# mimxrt10xx.net
KiCad netlist of a schematic drawn in Altium Designer
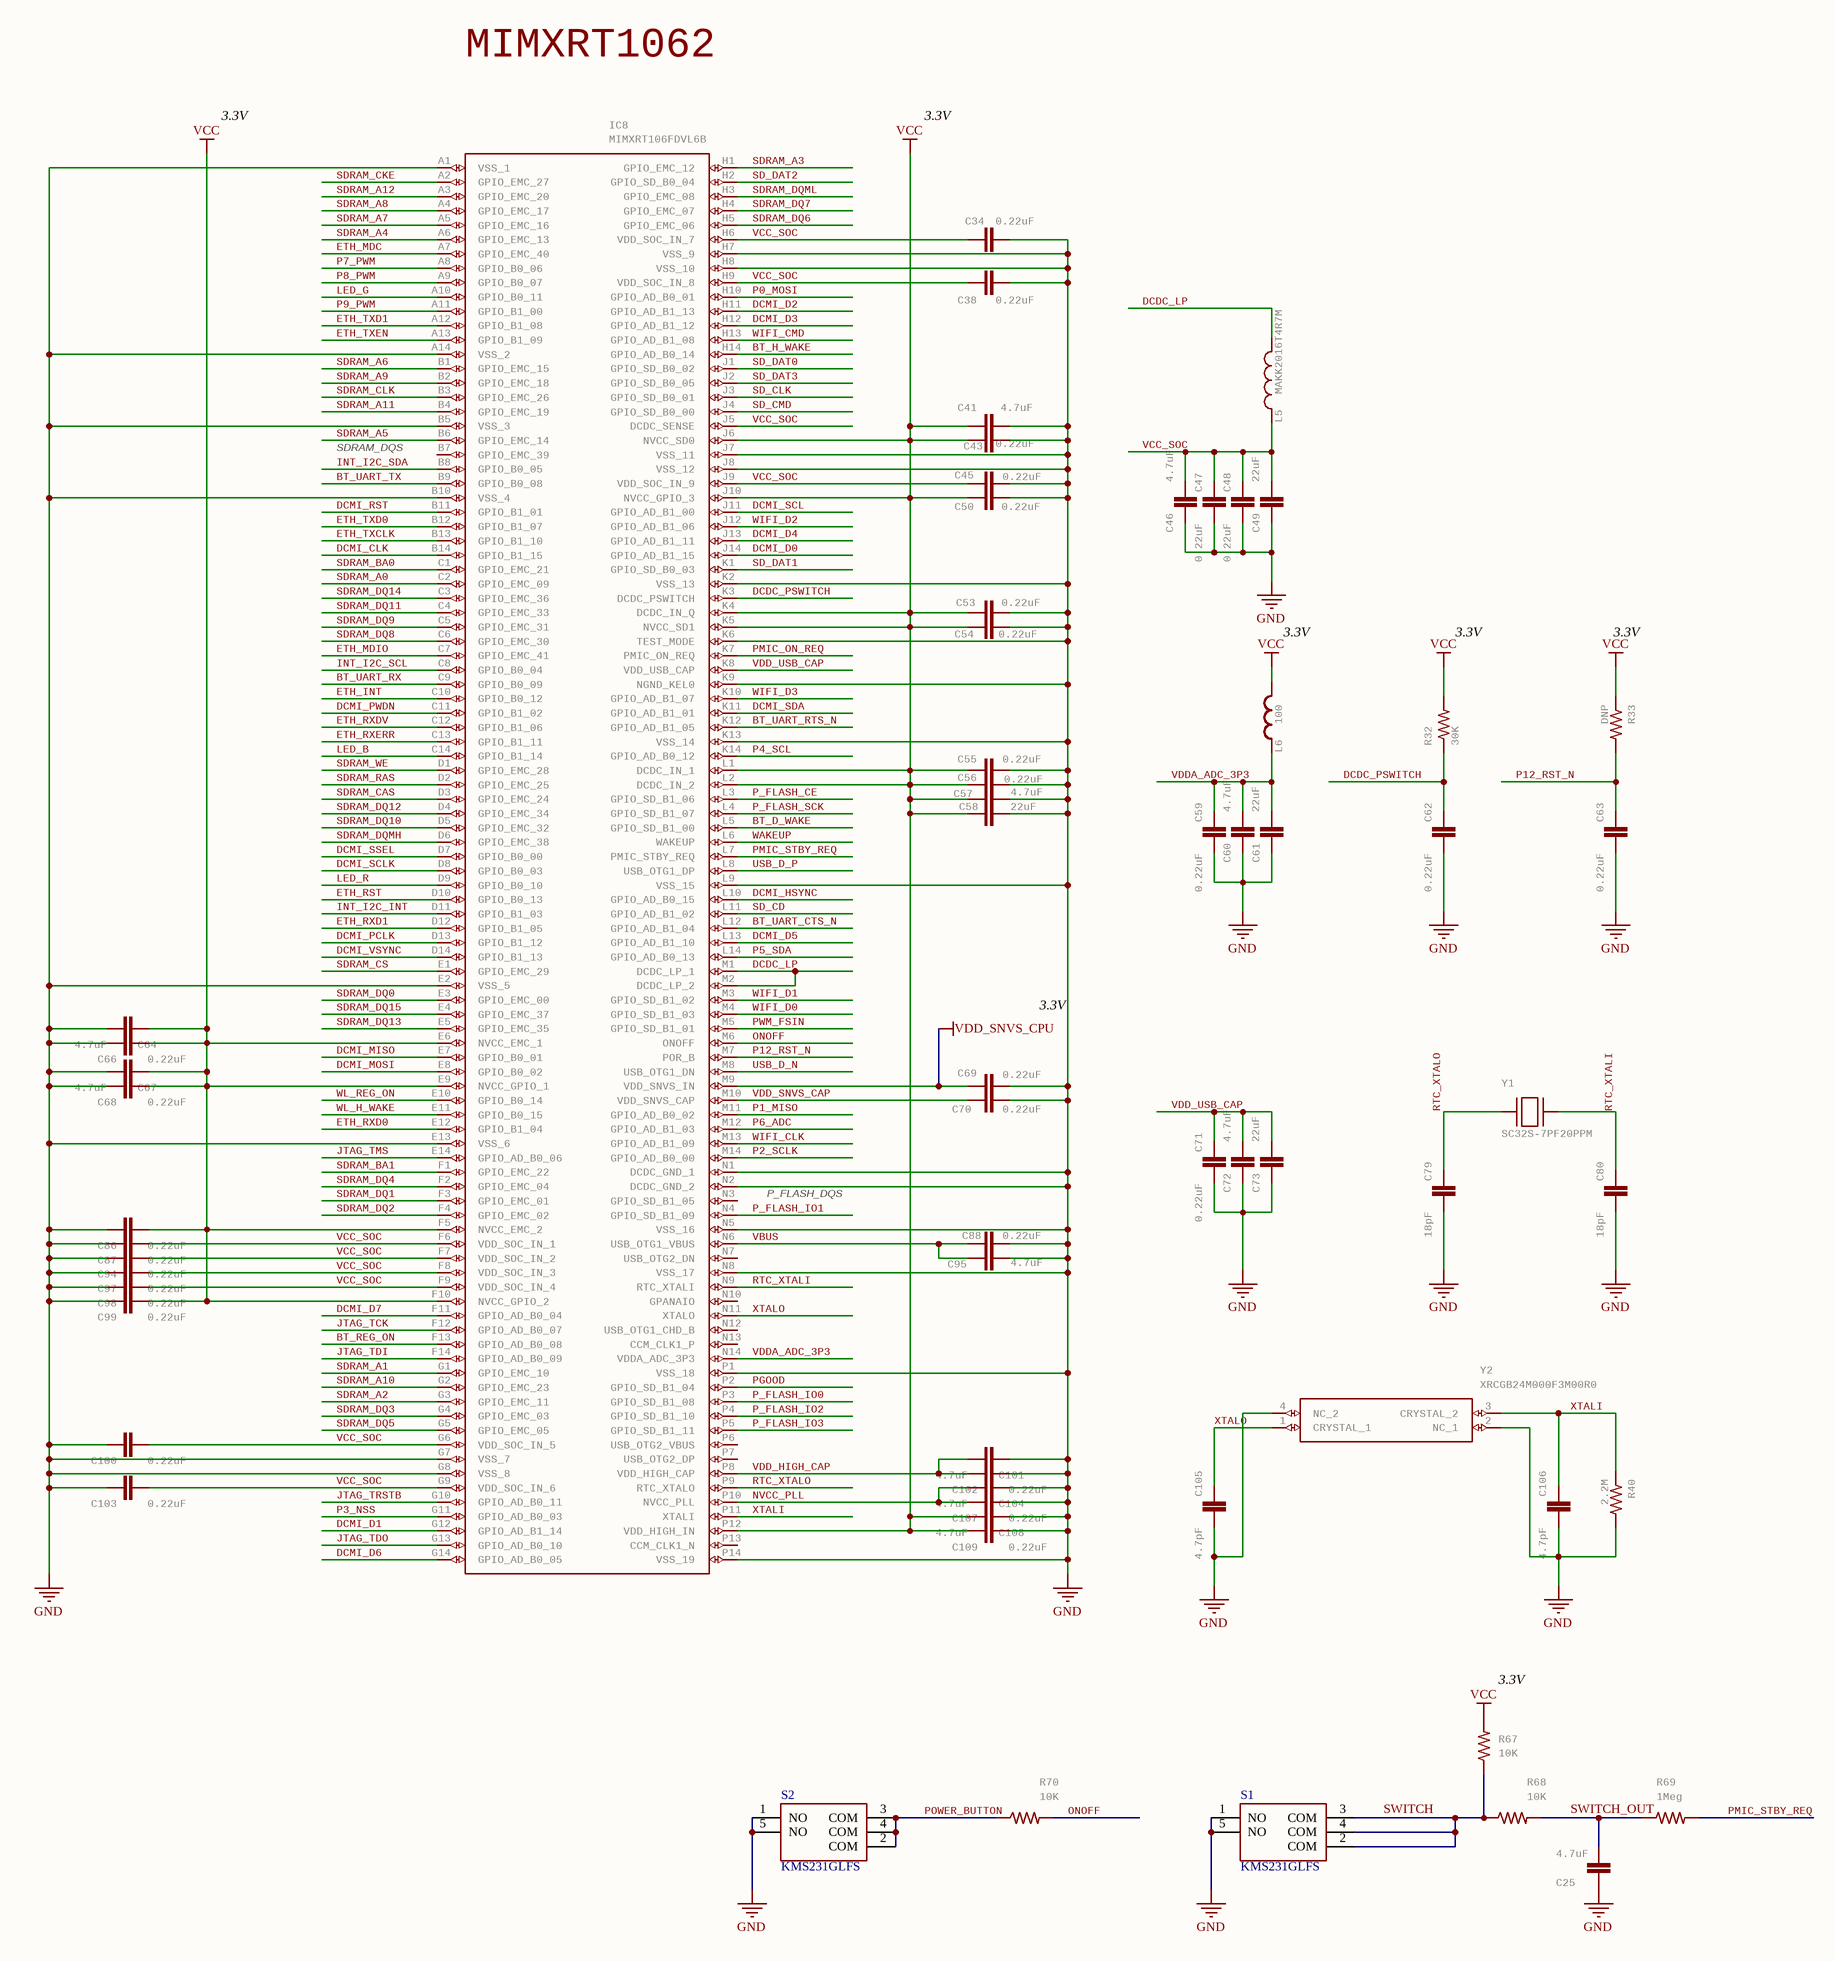
[diagram p0: mimxrt10xx.SchDoc]

(export (version "E")
  (design (tool "Eeschema 10.0.6"))
  (components
    (comp (ref "C25")
      (value "4.7uF")
      (footprint "0402-CAP")
      (description "CapacitorStandard 0603 ceramic capacitor, and 0.1\" leaded capacitor.")
      (fields (field (name "MPN") "JMK105BBJ475MV-F"))
      (libsource (lib "") (part "CAP0402-CAP_1"))
    )
    (comp (ref "C34")
      (value "0.22uF")
      (footprint "C0201")
      (description "CAPACITOR, European symbol")
      (fields (field (name "MPN") "GRM033R60J224ME15D"))
      (libsource (lib "rt10") (part "C-EUC0201"))
    )
    (comp (ref "C38")
      (value "0.22uF")
      (footprint "C0201")
      (description "CAPACITOR, European symbol")
      (fields (field (name "MPN") "GRM033R60J224ME15D"))
      (libsource (lib "rt10") (part "C-EUC0201"))
    )
    (comp (ref "C41")
      (value "4.7uF")
      (footprint "0402-CAP")
      (description "CapacitorStandard 0603 ceramic capacitor, and 0.1\" leaded capacitor.")
      (fields (field (name "MPN") "JMK105BBJ475MV-F"))
      (libsource (lib "rt10") (part "CAP0402-CAP"))
    )
    (comp (ref "C43")
      (value "0.22uF")
      (footprint "C0201")
      (description "CAPACITOR, European symbol")
      (fields (field (name "MPN") "GRM033R60J224ME15D"))
      (libsource (lib "rt10") (part "C-EUC0201"))
    )
    (comp (ref "C45")
      (value "0.22uF")
      (footprint "C0201")
      (description "CAPACITOR, European symbol")
      (fields (field (name "MPN") "GRM033R60J224ME15D"))
      (libsource (lib "rt10") (part "C-EUC0201"))
    )
    (comp (ref "C46")
      (value "4.7uF")
      (footprint "0402-CAP")
      (description "CapacitorStandard 0603 ceramic capacitor, and 0.1\" leaded capacitor.")
      (fields (field (name "MPN") "JMK105BBJ475MV-F"))
      (libsource (lib "") (part "CAP0402-CAP_1"))
    )
    (comp (ref "C47")
      (value "0.22uF")
      (footprint "C0201")
      (description "CAPACITOR, European symbol")
      (fields (field (name "MPN") "GRM033R60J224ME15D"))
      (libsource (lib "") (part "C-EUC0201_1"))
    )
    (comp (ref "C48")
      (value "0.22uF")
      (footprint "C0201")
      (description "CAPACITOR, European symbol")
      (fields (field (name "MPN") "GRM033R60J224ME15D"))
      (libsource (lib "") (part "C-EUC0201_1"))
    )
    (comp (ref "C49")
      (value "22uF")
      (footprint "0805")
      (fields (field (name "MPN") "CL21A226MQQNNNE"))
      (libsource (lib "rt10") (part "22UF-0805-6.3V-20%"))
    )
    (comp (ref "C50")
      (value "0.22uF")
      (footprint "C0201")
      (description "CAPACITOR, European symbol")
      (fields (field (name "MPN") "GRM033R60J224ME15D"))
      (libsource (lib "rt10") (part "C-EUC0201"))
    )
    (comp (ref "C53")
      (value "0.22uF")
      (footprint "C0201")
      (description "CAPACITOR, European symbol")
      (fields (field (name "MPN") "GRM033R60J224ME15D"))
      (libsource (lib "rt10") (part "C-EUC0201"))
    )
    (comp (ref "C54")
      (value "0.22uF")
      (footprint "C0201")
      (description "CAPACITOR, European symbol")
      (fields (field (name "MPN") "GRM033R60J224ME15D"))
      (libsource (lib "rt10") (part "C-EUC0201"))
    )
    (comp (ref "C55")
      (value "0.22uF")
      (footprint "C0201")
      (description "CAPACITOR, European symbol")
      (fields (field (name "MPN") "GRM033R60J224ME15D"))
      (libsource (lib "rt10") (part "C-EUC0201"))
    )
    (comp (ref "C56")
      (value "0.22uF")
      (footprint "C0201")
      (description "CAPACITOR, European symbol")
      (fields (field (name "MPN") "GRM033R60J224ME15D"))
      (libsource (lib "rt10") (part "C-EUC0201"))
    )
    (comp (ref "C57")
      (value "4.7uF")
      (footprint "0402-CAP")
      (description "CapacitorStandard 0603 ceramic capacitor, and 0.1\" leaded capacitor.")
      (fields (field (name "MPN") "JMK105BBJ475MV-F"))
      (libsource (lib "rt10") (part "CAP0402-CAP"))
    )
    (comp (ref "C58")
      (value "22uF")
      (footprint "0805")
      (fields (field (name "MPN") "CL21A226MQQNNNE"))
      (libsource (lib "") (part "22UF-0805-6.3V-20%_1"))
    )
    (comp (ref "C59")
      (value "0.22uF")
      (footprint "C0201")
      (description "CAPACITOR, European symbol")
      (fields (field (name "MPN") "GRM033R60J224ME15D"))
      (libsource (lib "") (part "C-EUC0201_1"))
    )
    (comp (ref "C60")
      (value "4.7uF")
      (footprint "0402-CAP")
      (description "CapacitorStandard 0603 ceramic capacitor, and 0.1\" leaded capacitor.")
      (fields (field (name "MPN") "JMK105BBJ475MV-F"))
      (libsource (lib "") (part "CAP0402-CAP_1"))
    )
    (comp (ref "C61")
      (value "22uF")
      (footprint "0805")
      (fields (field (name "MPN") "CL21A226MQQNNNE"))
      (libsource (lib "rt10") (part "22UF-0805-6.3V-20%"))
    )
    (comp (ref "C62")
      (value "0.22uF")
      (footprint "C0201")
      (description "CAPACITOR, European symbol")
      (fields (field (name "MPN") "GRM033R60J224ME15D"))
      (libsource (lib "") (part "C-EUC0201_1"))
    )
    (comp (ref "C63")
      (value "0.22uF")
      (footprint "C0201")
      (description "CAPACITOR, European symbol")
      (fields (field (name "MPN") "GRM033R60J224ME15D"))
      (libsource (lib "") (part "C-EUC0201_1"))
    )
    (comp (ref "C64")
      (value "4.7uF")
      (footprint "0402-CAP")
      (description "CapacitorStandard 0603 ceramic capacitor, and 0.1\" leaded capacitor.")
      (fields (field (name "MPN") "JMK105BBJ475MV-F"))
      (libsource (lib "rt10") (part "CAP0402-CAP"))
    )
    (comp (ref "C66")
      (value "0.22uF")
      (footprint "C0201")
      (description "CAPACITOR, European symbol")
      (fields (field (name "MPN") "GRM033R60J224ME15D"))
      (libsource (lib "rt10") (part "C-EUC0201"))
    )
    (comp (ref "C67")
      (value "4.7uF")
      (footprint "0402-CAP")
      (description "CapacitorStandard 0603 ceramic capacitor, and 0.1\" leaded capacitor.")
      (fields (field (name "MPN") "JMK105BBJ475MV-F"))
      (libsource (lib "rt10") (part "CAP0402-CAP"))
    )
    (comp (ref "C68")
      (value "0.22uF")
      (footprint "C0201")
      (description "CAPACITOR, European symbol")
      (fields (field (name "MPN") "GRM033R60J224ME15D"))
      (libsource (lib "rt10") (part "C-EUC0201"))
    )
    (comp (ref "C69")
      (value "0.22uF")
      (footprint "C0201")
      (description "CAPACITOR, European symbol")
      (fields (field (name "MPN") "GRM033R60J224ME15D"))
      (libsource (lib "rt10") (part "C-EUC0201"))
    )
    (comp (ref "C70")
      (value "0.22uF")
      (footprint "C0201")
      (description "CAPACITOR, European symbol")
      (fields (field (name "MPN") "GRM033R60J224ME15D"))
      (libsource (lib "rt10") (part "C-EUC0201"))
    )
    (comp (ref "C71")
      (value "0.22uF")
      (footprint "C0201")
      (description "CAPACITOR, European symbol")
      (fields (field (name "MPN") "GRM033R60J224ME15D"))
      (libsource (lib "") (part "C-EUC0201_1"))
    )
    (comp (ref "C72")
      (value "4.7uF")
      (footprint "0402-CAP")
      (description "CapacitorStandard 0603 ceramic capacitor, and 0.1\" leaded capacitor.")
      (fields (field (name "MPN") "JMK105BBJ475MV-F"))
      (libsource (lib "") (part "CAP0402-CAP_1"))
    )
    (comp (ref "C73")
      (value "22uF")
      (footprint "0805")
      (fields (field (name "MPN") "CL21A226MQQNNNE"))
      (libsource (lib "rt10") (part "22UF-0805-6.3V-20%"))
    )
    (comp (ref "C79")
      (value "18pF")
      (footprint "C0201")
      (description "CAPACITOR, European symbol")
      (fields (field (name "MPN") "GRM0335C1E180JA01D"))
      (libsource (lib "") (part "C-EUC0201_1"))
    )
    (comp (ref "C80")
      (value "18pF")
      (footprint "C0201")
      (description "CAPACITOR, European symbol")
      (fields (field (name "MPN") "GRM0335C1E180JA01D"))
      (libsource (lib "") (part "C-EUC0201_1"))
    )
    (comp (ref "C86")
      (value "0.22uF")
      (footprint "C0201")
      (description "CAPACITOR, European symbol")
      (fields (field (name "MPN") "GRM033R60J224ME15D"))
      (libsource (lib "rt10") (part "C-EUC0201"))
    )
    (comp (ref "C87")
      (value "0.22uF")
      (footprint "C0201")
      (description "CAPACITOR, European symbol")
      (fields (field (name "MPN") "GRM033R60J224ME15D"))
      (libsource (lib "rt10") (part "C-EUC0201"))
    )
    (comp (ref "C88")
      (value "0.22uF")
      (footprint "C0201")
      (description "CAPACITOR, European symbol")
      (fields (field (name "MPN") "GRM033R60J224ME15D"))
      (libsource (lib "rt10") (part "C-EUC0201"))
    )
    (comp (ref "C94")
      (value "0.22uF")
      (footprint "C0201")
      (description "CAPACITOR, European symbol")
      (fields (field (name "MPN") "GRM033R60J224ME15D"))
      (libsource (lib "rt10") (part "C-EUC0201"))
    )
    (comp (ref "C95")
      (value "4.7uF")
      (footprint "0402-CAP")
      (description "CapacitorStandard 0603 ceramic capacitor, and 0.1\" leaded capacitor.")
      (fields (field (name "MPN") "JMK105BBJ475MV-F"))
      (libsource (lib "rt10") (part "CAP0402-CAP"))
    )
    (comp (ref "C97")
      (value "0.22uF")
      (footprint "C0201")
      (description "CAPACITOR, European symbol")
      (fields (field (name "MPN") "GRM033R60J224ME15D"))
      (libsource (lib "rt10") (part "C-EUC0201"))
    )
    (comp (ref "C98")
      (value "0.22uF")
      (footprint "C0201")
      (description "CAPACITOR, European symbol")
      (fields (field (name "MPN") "GRM033R60J224ME15D"))
      (libsource (lib "rt10") (part "C-EUC0201"))
    )
    (comp (ref "C99")
      (value "0.22uF")
      (footprint "C0201")
      (description "CAPACITOR, European symbol")
      (fields (field (name "MPN") "GRM033R60J224ME15D"))
      (libsource (lib "rt10") (part "C-EUC0201"))
    )
    (comp (ref "C100")
      (value "0.22uF")
      (footprint "C0201")
      (description "CAPACITOR, European symbol")
      (fields (field (name "MPN") "GRM033R60J224ME15D"))
      (libsource (lib "rt10") (part "C-EUC0201"))
    )
    (comp (ref "C101")
      (value "4.7uF")
      (footprint "0402-CAP")
      (description "CapacitorStandard 0603 ceramic capacitor, and 0.1\" leaded capacitor.")
      (fields (field (name "MPN") "JMK105BBJ475MV-F"))
      (libsource (lib "rt10") (part "CAP0402-CAP"))
    )
    (comp (ref "C102")
      (value "0.22uF")
      (footprint "C0201")
      (description "CAPACITOR, European symbol")
      (fields (field (name "MPN") "GRM033R60J224ME15D"))
      (libsource (lib "rt10") (part "C-EUC0201"))
    )
    (comp (ref "C103")
      (value "0.22uF")
      (footprint "C0201")
      (description "CAPACITOR, European symbol")
      (fields (field (name "MPN") "GRM033R60J224ME15D"))
      (libsource (lib "rt10") (part "C-EUC0201"))
    )
    (comp (ref "C104")
      (value "4.7uF")
      (footprint "0402-CAP")
      (description "CapacitorStandard 0603 ceramic capacitor, and 0.1\" leaded capacitor.")
      (fields (field (name "MPN") "JMK105BBJ475MV-F"))
      (libsource (lib "rt10") (part "CAP0402-CAP"))
    )
    (comp (ref "C105")
      (value "4.7pF")
      (footprint "C0201")
      (description "CAPACITOR, European symbol")
      (fields (field (name "MPN") "GRM0335C1E4R7CA01D"))
      (libsource (lib "") (part "C-EUC0201_1"))
    )
    (comp (ref "C106")
      (value "4.7pF")
      (footprint "C0201")
      (description "CAPACITOR, European symbol")
      (fields (field (name "MPN") "GRM0335C1E4R7CA01D"))
      (libsource (lib "") (part "C-EUC0201_1"))
    )
    (comp (ref "C107")
      (value "0.22uF")
      (footprint "C0201")
      (description "CAPACITOR, European symbol")
      (fields (field (name "MPN") "GRM033R60J224ME15D"))
      (libsource (lib "rt10") (part "C-EUC0201"))
    )
    (comp (ref "C108")
      (value "4.7uF")
      (footprint "0402-CAP")
      (description "CapacitorStandard 0603 ceramic capacitor, and 0.1\" leaded capacitor.")
      (fields (field (name "MPN") "JMK105BBJ475MV-F"))
      (libsource (lib "rt10") (part "CAP0402-CAP"))
    )
    (comp (ref "C109")
      (value "0.22uF")
      (footprint "C0201")
      (description "CAPACITOR, European symbol")
      (fields (field (name "MPN") "GRM033R60J224ME15D"))
      (libsource (lib "rt10") (part "C-EUC0201"))
    )
    (comp (ref "IC8")
      (value "MIMXRT106FDVL6B")
      (footprint "BGA196C65P14X14_1000X1000X143")
      (libsource (lib "rt10") (part "MIMXRT1052DVL6B"))
    )
    (comp (ref "L5")
      (value "MAKK2016T4R7M")
      (footprint "INDC2016X100N")
      (description "INDUCTOR, METAL CORE, SHIELDED, SMD HIGH CURRENT, 4.7uH, 20%, TR Check availability")
      (fields (field (name "MF") "Taiyo Yuden"))
      (libsource (lib "rt10") (part "MAKK2016T4R7M"))
    )
    (comp (ref "L6")
      (value "100")
      (footprint "C0402")
      (fields (field (name "MPN") "MFBM1V1005-101-R"))
      (libsource (lib "rt10") (part "INDUCTOR0402"))
    )
    (comp (ref "R32")
      (value "30K")
      (footprint "0201-RES")
      (description "ResistorBasic schematic elements and footprints for 0603, 1206, and PTH resistors.")
      (fields (field (name "MPN") "RC0201FR-0730KL"))
      (libsource (lib "rt10") (part "RESISTOR0402-RES"))
    )
    (comp (ref "R33")
      (value "DNP")
      (footprint "0402-RES")
      (description "ResistorBasic schematic elements and footprints for 0603, 1206, and PTH resistors.")
      (libsource (lib "rt10") (part "RESISTOR0402-RES"))
    )
    (comp (ref "R40")
      (value "2.2M")
      (footprint "0402-RES")
      (description "ResistorBasic schematic elements and footprints for 0603, 1206, and PTH resistors.")
      (fields (field (name "MPN") "RC0402FR-072M2L"))
      (libsource (lib "rt10") (part "RESISTOR0402-RES"))
    )
    (comp (ref "R67")
      (value "10K")
      (footprint "0402-RES")
      (description "ResistorBasic schematic elements and footprints for 0603, 1206, and PTH resistors.")
      (fields (field (name "MPN") "AC0402FR-1310K"))
      (libsource (lib "rt10") (part "RESISTOR0402-RES"))
    )
    (comp (ref "R68")
      (value "10K")
      (footprint "0402-RES")
      (description "ResistorBasic schematic elements and footprints for 0603, 1206, and PTH resistors.")
      (fields (field (name "MPN") "AC0402FR-1310K"))
      (libsource (lib "rt10") (part "RESISTOR0402-RES"))
    )
    (comp (ref "R69")
      (value "1Meg")
      (footprint "0402-RES")
      (description "ResistorBasic schematic elements and footprints for 0603, 1206, and PTH resistors.")
      (fields (field (name "MPN") "CRCW04021M00FKEDC"))
      (libsource (lib "rt10") (part "RESISTOR0402-RES"))
    )
    (comp (ref "R70")
      (value "10K")
      (footprint "0402-RES")
      (description "ResistorBasic schematic elements and footprints for 0603, 1206, and PTH resistors.")
      (fields (field (name "MPN") "AC0402FR-1310K"))
      (libsource (lib "rt10") (part "RESISTOR0402-RES"))
    )
    (comp (ref "S1")
      (value "KMS231GLFS")
      (footprint "KMS231GLFS")
      (libsource (lib "rt10") (part "KMS231GLFS"))
    )
    (comp (ref "S2")
      (value "KMS231GLFS")
      (footprint "KMS231GLFS")
      (libsource (lib "rt10") (part "KMS231GLFS"))
    )
    (comp (ref "Y1")
      (value "SC32S-7PF20PPM")
      (footprint "XTAL_ABS07-32.768KHZ-7-T")
      (description "Check availability")
      (fields (field (name "MF") "Abracon") (field (name "MP") "ABS07-32.768KHZ-7-T"))
      (libsource (lib "rt10") (part "ABS07-32.768KHZ-7-T"))
    )
    (comp (ref "Y2")
      (value "XRCGB24M000F3M00R0")
      (footprint "XRCGB24M000F3M00R0")
      (description "Murata 24MHz Crystal +/-30ppm SMD 4-Pin 2 x 1.6 x 0.7mm   Source:  Datasheet")
      (fields (field (name "MOUSER_PART_NUMBER") "81-XRCGB24M000F3M0R0"))
      (libsource (lib "rt10") (part "XRCGB24M000F3M00R0"))
    )
  )
  (nets
    (net (code "1") (name "/BT_D_WAKE") (class "Default")
      (node (ref "IC8") (pin "L5") (pinfunction "GPIO_SD_B1_00_L5") (pintype "bidirectional"))
    )
    (net (code "2") (name "/BT_H_WAKE") (class "Default")
      (node (ref "IC8") (pin "H14") (pinfunction "GPIO_AD_B0_14_H14") (pintype "bidirectional"))
    )
    (net (code "3") (name "/BT_REG_ON") (class "Default")
      (node (ref "IC8") (pin "F13") (pinfunction "GPIO_AD_B0_08_F13") (pintype "bidirectional"))
    )
    (net (code "4") (name "/BT_UART_CTS_N") (class "Default")
      (node (ref "IC8") (pin "L12") (pinfunction "GPIO_AD_B1_04_L12") (pintype "bidirectional"))
    )
    (net (code "5") (name "/BT_UART_RTS_N") (class "Default")
      (node (ref "IC8") (pin "K12") (pinfunction "GPIO_AD_B1_05_K12") (pintype "bidirectional"))
    )
    (net (code "6") (name "/BT_UART_RX") (class "Default")
      (node (ref "IC8") (pin "C9") (pinfunction "GPIO_B0_09_C9") (pintype "bidirectional"))
    )
    (net (code "7") (name "/BT_UART_TX") (class "Default")
      (node (ref "IC8") (pin "B9") (pinfunction "GPIO_B0_08_B9") (pintype "bidirectional"))
    )
    (net (code "8") (name "/DCDC_LP") (class "Default")
      (node (ref "IC8") (pin "M1") (pinfunction "DCDC_LP_1_M1") (pintype "bidirectional"))
      (node (ref "IC8") (pin "M2") (pinfunction "DCDC_LP_2_M2") (pintype "bidirectional"))
      (node (ref "L5") (pin "2") (pinfunction "2_2") (pintype "passive"))
    )
    (net (code "9") (name "/DCDC_PSWITCH") (class "Default")
      (node (ref "C62") (pin "1") (pinfunction "1_1") (pintype "passive"))
      (node (ref "IC8") (pin "K3") (pinfunction "DCDC_PSWITCH_K3") (pintype "bidirectional"))
      (node (ref "R32") (pin "1") (pinfunction "1_1") (pintype "passive"))
    )
    (net (code "10") (name "/DCMI_CLK") (class "Default")
      (node (ref "IC8") (pin "B14") (pinfunction "GPIO_B1_15_B14") (pintype "bidirectional"))
    )
    (net (code "11") (name "/DCMI_D0") (class "Default")
      (node (ref "IC8") (pin "J14") (pinfunction "GPIO_AD_B1_15_J14") (pintype "bidirectional"))
    )
    (net (code "12") (name "/DCMI_D1") (class "Default")
      (node (ref "IC8") (pin "G12") (pinfunction "GPIO_AD_B1_14_G12") (pintype "bidirectional"))
    )
    (net (code "13") (name "/DCMI_D2") (class "Default")
      (node (ref "IC8") (pin "H11") (pinfunction "GPIO_AD_B1_13_H11") (pintype "bidirectional"))
    )
    (net (code "14") (name "/DCMI_D3") (class "Default")
      (node (ref "IC8") (pin "H12") (pinfunction "GPIO_AD_B1_12_H12") (pintype "bidirectional"))
    )
    (net (code "15") (name "/DCMI_D4") (class "Default")
      (node (ref "IC8") (pin "J13") (pinfunction "GPIO_AD_B1_11_J13") (pintype "bidirectional"))
    )
    (net (code "16") (name "/DCMI_D5") (class "Default")
      (node (ref "IC8") (pin "L13") (pinfunction "GPIO_AD_B1_10_L13") (pintype "bidirectional"))
    )
    (net (code "17") (name "/DCMI_D6") (class "Default")
      (node (ref "IC8") (pin "G14") (pinfunction "GPIO_AD_B0_05_G14") (pintype "bidirectional"))
    )
    (net (code "18") (name "/DCMI_D7") (class "Default")
      (node (ref "IC8") (pin "F11") (pinfunction "GPIO_AD_B0_04_F11") (pintype "bidirectional"))
    )
    (net (code "19") (name "/DCMI_HSYNC") (class "Default")
      (node (ref "IC8") (pin "L10") (pinfunction "GPIO_AD_B0_15_L10") (pintype "bidirectional"))
    )
    (net (code "20") (name "/DCMI_MISO") (class "Default")
      (node (ref "IC8") (pin "E7") (pinfunction "GPIO_B0_01_E7") (pintype "bidirectional"))
    )
    (net (code "21") (name "/DCMI_MOSI") (class "Default")
      (node (ref "IC8") (pin "E8") (pinfunction "GPIO_B0_02_E8") (pintype "bidirectional"))
    )
    (net (code "22") (name "/DCMI_PCLK") (class "Default")
      (node (ref "IC8") (pin "D13") (pinfunction "GPIO_B1_12_D13") (pintype "bidirectional"))
    )
    (net (code "23") (name "/DCMI_PWDN") (class "Default")
      (node (ref "IC8") (pin "C11") (pinfunction "GPIO_B1_02_C11") (pintype "bidirectional"))
    )
    (net (code "24") (name "/DCMI_RST") (class "Default")
      (node (ref "IC8") (pin "B11") (pinfunction "GPIO_B1_01_B11") (pintype "bidirectional"))
    )
    (net (code "25") (name "/DCMI_SCL") (class "Default")
      (node (ref "IC8") (pin "J11") (pinfunction "GPIO_AD_B1_00_J11") (pintype "bidirectional"))
    )
    (net (code "26") (name "/DCMI_SCLK") (class "Default")
      (node (ref "IC8") (pin "D8") (pinfunction "GPIO_B0_03_D8") (pintype "bidirectional"))
    )
    (net (code "27") (name "/DCMI_SDA") (class "Default")
      (node (ref "IC8") (pin "K11") (pinfunction "GPIO_AD_B1_01_K11") (pintype "bidirectional"))
    )
    (net (code "28") (name "/DCMI_SSEL") (class "Default")
      (node (ref "IC8") (pin "D7") (pinfunction "GPIO_B0_00_D7") (pintype "bidirectional"))
    )
    (net (code "29") (name "/DCMI_VSYNC") (class "Default")
      (node (ref "IC8") (pin "D14") (pinfunction "GPIO_B1_13_D14") (pintype "bidirectional"))
    )
    (net (code "30") (name "/ETH_INT") (class "Default")
      (node (ref "IC8") (pin "C10") (pinfunction "GPIO_B0_12_C10") (pintype "bidirectional"))
    )
    (net (code "31") (name "/ETH_MDC") (class "Default")
      (node (ref "IC8") (pin "A7") (pinfunction "GPIO_EMC_40_A7") (pintype "bidirectional"))
    )
    (net (code "32") (name "/ETH_MDIO") (class "Default")
      (node (ref "IC8") (pin "C7") (pinfunction "GPIO_EMC_41_C7") (pintype "bidirectional"))
    )
    (net (code "33") (name "/ETH_RST") (class "Default")
      (node (ref "IC8") (pin "D10") (pinfunction "GPIO_B0_13_D10") (pintype "bidirectional"))
    )
    (net (code "34") (name "/ETH_RXD0") (class "Default")
      (node (ref "IC8") (pin "E12") (pinfunction "GPIO_B1_04_E12") (pintype "bidirectional"))
    )
    (net (code "35") (name "/ETH_RXD1") (class "Default")
      (node (ref "IC8") (pin "D12") (pinfunction "GPIO_B1_05_D12") (pintype "bidirectional"))
    )
    (net (code "36") (name "/ETH_RXDV") (class "Default")
      (node (ref "IC8") (pin "C12") (pinfunction "GPIO_B1_06_C12") (pintype "bidirectional"))
    )
    (net (code "37") (name "/ETH_RXERR") (class "Default")
      (node (ref "IC8") (pin "C13") (pinfunction "GPIO_B1_11_C13") (pintype "bidirectional"))
    )
    (net (code "38") (name "/ETH_TXCLK") (class "Default")
      (node (ref "IC8") (pin "B13") (pinfunction "GPIO_B1_10_B13") (pintype "bidirectional"))
    )
    (net (code "39") (name "/ETH_TXD0") (class "Default")
      (node (ref "IC8") (pin "B12") (pinfunction "GPIO_B1_07_B12") (pintype "bidirectional"))
    )
    (net (code "40") (name "/ETH_TXD1") (class "Default")
      (node (ref "IC8") (pin "A12") (pinfunction "GPIO_B1_08_A12") (pintype "bidirectional"))
    )
    (net (code "41") (name "/ETH_TXEN") (class "Default")
      (node (ref "IC8") (pin "A13") (pinfunction "GPIO_B1_09_A13") (pintype "bidirectional"))
    )
    (net (code "42") (name "/INT_I2C_INT") (class "Default")
      (node (ref "IC8") (pin "D11") (pinfunction "GPIO_B1_03_D11") (pintype "bidirectional"))
    )
    (net (code "43") (name "/INT_I2C_SCL") (class "Default")
      (node (ref "IC8") (pin "C8") (pinfunction "GPIO_B0_04_C8") (pintype "bidirectional"))
    )
    (net (code "44") (name "/INT_I2C_SDA") (class "Default")
      (node (ref "IC8") (pin "B8") (pinfunction "GPIO_B0_05_B8") (pintype "bidirectional"))
    )
    (net (code "45") (name "/JTAG_TCK") (class "Default")
      (node (ref "IC8") (pin "F12") (pinfunction "GPIO_AD_B0_07_F12") (pintype "bidirectional"))
    )
    (net (code "46") (name "/JTAG_TDI") (class "Default")
      (node (ref "IC8") (pin "F14") (pinfunction "GPIO_AD_B0_09_F14") (pintype "bidirectional"))
    )
    (net (code "47") (name "/JTAG_TDO") (class "Default")
      (node (ref "IC8") (pin "G13") (pinfunction "GPIO_AD_B0_10_G13") (pintype "bidirectional"))
    )
    (net (code "48") (name "/JTAG_TMS") (class "Default")
      (node (ref "IC8") (pin "E14") (pinfunction "GPIO_AD_B0_06_E14") (pintype "bidirectional"))
    )
    (net (code "49") (name "/JTAG_TRSTB") (class "Default")
      (node (ref "IC8") (pin "G10") (pinfunction "GPIO_AD_B0_11_G10") (pintype "bidirectional"))
    )
    (net (code "50") (name "/LED_B") (class "Default")
      (node (ref "IC8") (pin "C14") (pinfunction "GPIO_B1_14_C14") (pintype "bidirectional"))
    )
    (net (code "51") (name "/LED_G") (class "Default")
      (node (ref "IC8") (pin "A10") (pinfunction "GPIO_B0_11_A10") (pintype "bidirectional"))
    )
    (net (code "52") (name "/LED_R") (class "Default")
      (node (ref "IC8") (pin "D9") (pinfunction "GPIO_B0_10_D9") (pintype "bidirectional"))
    )
    (net (code "53") (name "/NVCC_PLL") (class "Default")
      (node (ref "C104") (pin "2") (pinfunction "2_2") (pintype "passive"))
      (node (ref "C107") (pin "1") (pinfunction "1_1") (pintype "passive"))
      (node (ref "IC8") (pin "P10") (pinfunction "NVCC_PLL_P10") (pintype "bidirectional"))
    )
    (net (code "54") (name "/ONOFF") (class "Default")
      (node (ref "IC8") (pin "M6") (pinfunction "ONOFF_M6") (pintype "bidirectional"))
      (node (ref "R70") (pin "2") (pinfunction "2_2") (pintype "passive"))
    )
    (net (code "55") (name "/P0_MOSI") (class "Default")
      (node (ref "IC8") (pin "H10") (pinfunction "GPIO_AD_B0_01_H10") (pintype "bidirectional"))
    )
    (net (code "56") (name "/P1_MISO") (class "Default")
      (node (ref "IC8") (pin "M11") (pinfunction "GPIO_AD_B0_02_M11") (pintype "bidirectional"))
    )
    (net (code "57") (name "/P2_SCLK") (class "Default")
      (node (ref "IC8") (pin "M14") (pinfunction "GPIO_AD_B0_00_M14") (pintype "bidirectional"))
    )
    (net (code "58") (name "/P3_NSS") (class "Default")
      (node (ref "IC8") (pin "G11") (pinfunction "GPIO_AD_B0_03_G11") (pintype "bidirectional"))
    )
    (net (code "59") (name "/P4_SCL") (class "Default")
      (node (ref "IC8") (pin "K14") (pinfunction "GPIO_AD_B0_12_K14") (pintype "bidirectional"))
    )
    (net (code "60") (name "/P5_SDA") (class "Default")
      (node (ref "IC8") (pin "L14") (pinfunction "GPIO_AD_B0_13_L14") (pintype "bidirectional"))
    )
    (net (code "61") (name "/P6_ADC") (class "Default")
      (node (ref "IC8") (pin "M12") (pinfunction "GPIO_AD_B1_03_M12") (pintype "bidirectional"))
    )
    (net (code "62") (name "/P7_PWM") (class "Default")
      (node (ref "IC8") (pin "A8") (pinfunction "GPIO_B0_06_A8") (pintype "bidirectional"))
    )
    (net (code "63") (name "/P8_PWM") (class "Default")
      (node (ref "IC8") (pin "A9") (pinfunction "GPIO_B0_07_A9") (pintype "bidirectional"))
    )
    (net (code "64") (name "/P9_PWM") (class "Default")
      (node (ref "IC8") (pin "A11") (pinfunction "GPIO_B1_00_A11") (pintype "bidirectional"))
    )
    (net (code "65") (name "/P12_RST_N") (class "Default")
      (node (ref "C63") (pin "1") (pinfunction "1_1") (pintype "passive"))
      (node (ref "IC8") (pin "M7") (pinfunction "POR_B_M7") (pintype "bidirectional"))
      (node (ref "R33") (pin "2") (pinfunction "2_2") (pintype "passive"))
    )
    (net (code "66") (name "/PGOOD") (class "Default")
      (node (ref "IC8") (pin "P2") (pinfunction "GPIO_SD_B1_04_P2") (pintype "bidirectional"))
    )
    (net (code "67") (name "/PMIC_ON_REQ") (class "Default")
      (node (ref "IC8") (pin "K7") (pinfunction "PMIC_ON_REQ_K7") (pintype "bidirectional"))
    )
    (net (code "68") (name "/PMIC_STBY_REQ") (class "Default")
      (node (ref "IC8") (pin "L7") (pinfunction "PMIC_STBY_REQ_L7") (pintype "bidirectional"))
      (node (ref "R69") (pin "2") (pinfunction "2_2") (pintype "passive"))
    )
    (net (code "69") (name "/POWER_BUTTON") (class "Default")
      (node (ref "R70") (pin "1") (pinfunction "1_1") (pintype "passive"))
      (node (ref "S2") (pin "2") (pinfunction "COM_2") (pintype "passive"))
      (node (ref "S2") (pin "3") (pinfunction "COM_3") (pintype "passive"))
      (node (ref "S2") (pin "4") (pinfunction "COM_4") (pintype "passive"))
    )
    (net (code "70") (name "/PWM_FSIN") (class "Default")
      (node (ref "IC8") (pin "M5") (pinfunction "GPIO_SD_B1_01_M5") (pintype "bidirectional"))
    )
    (net (code "71") (name "/P_FLASH_CE") (class "Default")
      (node (ref "IC8") (pin "L3") (pinfunction "GPIO_SD_B1_06_L3") (pintype "bidirectional"))
    )
    (net (code "72") (name "/P_FLASH_IO0") (class "Default")
      (node (ref "IC8") (pin "P3") (pinfunction "GPIO_SD_B1_08_P3") (pintype "bidirectional"))
    )
    (net (code "73") (name "/P_FLASH_IO1") (class "Default")
      (node (ref "IC8") (pin "N4") (pinfunction "GPIO_SD_B1_09_N4") (pintype "bidirectional"))
    )
    (net (code "74") (name "/P_FLASH_IO2") (class "Default")
      (node (ref "IC8") (pin "P4") (pinfunction "GPIO_SD_B1_10_P4") (pintype "bidirectional"))
    )
    (net (code "75") (name "/P_FLASH_IO3") (class "Default")
      (node (ref "IC8") (pin "P5") (pinfunction "GPIO_SD_B1_11_P5") (pintype "bidirectional"))
    )
    (net (code "76") (name "/P_FLASH_SCK") (class "Default")
      (node (ref "IC8") (pin "L4") (pinfunction "GPIO_SD_B1_07_L4") (pintype "bidirectional"))
    )
    (net (code "77") (name "/RTC_XTALI") (class "Default")
      (node (ref "C80") (pin "1") (pinfunction "1_1") (pintype "passive"))
      (node (ref "IC8") (pin "N9") (pinfunction "RTC_XTALI_N9") (pintype "bidirectional"))
      (node (ref "Y1") (pin "2") (pinfunction "2_2") (pintype "passive"))
    )
    (net (code "78") (name "/RTC_XTALO") (class "Default")
      (node (ref "C79") (pin "1") (pinfunction "1_1") (pintype "passive"))
      (node (ref "IC8") (pin "P9") (pinfunction "RTC_XTALO_P9") (pintype "bidirectional"))
      (node (ref "Y1") (pin "1") (pinfunction "1_1") (pintype "passive"))
    )
    (net (code "79") (name "/SDRAM_A0") (class "Default")
      (node (ref "IC8") (pin "C2") (pinfunction "GPIO_EMC_09_C2") (pintype "bidirectional"))
    )
    (net (code "80") (name "/SDRAM_A1") (class "Default")
      (node (ref "IC8") (pin "G1") (pinfunction "GPIO_EMC_10_G1") (pintype "bidirectional"))
    )
    (net (code "81") (name "/SDRAM_A2") (class "Default")
      (node (ref "IC8") (pin "G3") (pinfunction "GPIO_EMC_11_G3") (pintype "bidirectional"))
    )
    (net (code "82") (name "/SDRAM_A3") (class "Default")
      (node (ref "IC8") (pin "H1") (pinfunction "GPIO_EMC_12_H1") (pintype "bidirectional"))
    )
    (net (code "83") (name "/SDRAM_A4") (class "Default")
      (node (ref "IC8") (pin "A6") (pinfunction "GPIO_EMC_13_A6") (pintype "bidirectional"))
    )
    (net (code "84") (name "/SDRAM_A5") (class "Default")
      (node (ref "IC8") (pin "B6") (pinfunction "GPIO_EMC_14_B6") (pintype "bidirectional"))
    )
    (net (code "85") (name "/SDRAM_A6") (class "Default")
      (node (ref "IC8") (pin "B1") (pinfunction "GPIO_EMC_15_B1") (pintype "bidirectional"))
    )
    (net (code "86") (name "/SDRAM_A7") (class "Default")
      (node (ref "IC8") (pin "A5") (pinfunction "GPIO_EMC_16_A5") (pintype "bidirectional"))
    )
    (net (code "87") (name "/SDRAM_A8") (class "Default")
      (node (ref "IC8") (pin "A4") (pinfunction "GPIO_EMC_17_A4") (pintype "bidirectional"))
    )
    (net (code "88") (name "/SDRAM_A9") (class "Default")
      (node (ref "IC8") (pin "B2") (pinfunction "GPIO_EMC_18_B2") (pintype "bidirectional"))
    )
    (net (code "89") (name "/SDRAM_A10") (class "Default")
      (node (ref "IC8") (pin "G2") (pinfunction "GPIO_EMC_23_G2") (pintype "bidirectional"))
    )
    (net (code "90") (name "/SDRAM_A11") (class "Default")
      (node (ref "IC8") (pin "B4") (pinfunction "GPIO_EMC_19_B4") (pintype "bidirectional"))
    )
    (net (code "91") (name "/SDRAM_A12") (class "Default")
      (node (ref "IC8") (pin "A3") (pinfunction "GPIO_EMC_20_A3") (pintype "bidirectional"))
    )
    (net (code "92") (name "/SDRAM_BA0") (class "Default")
      (node (ref "IC8") (pin "C1") (pinfunction "GPIO_EMC_21_C1") (pintype "bidirectional"))
    )
    (net (code "93") (name "/SDRAM_BA1") (class "Default")
      (node (ref "IC8") (pin "F1") (pinfunction "GPIO_EMC_22_F1") (pintype "bidirectional"))
    )
    (net (code "94") (name "/SDRAM_CAS") (class "Default")
      (node (ref "IC8") (pin "D3") (pinfunction "GPIO_EMC_24_D3") (pintype "bidirectional"))
    )
    (net (code "95") (name "/SDRAM_CKE") (class "Default")
      (node (ref "IC8") (pin "A2") (pinfunction "GPIO_EMC_27_A2") (pintype "bidirectional"))
    )
    (net (code "96") (name "/SDRAM_CLK") (class "Default")
      (node (ref "IC8") (pin "B3") (pinfunction "GPIO_EMC_26_B3") (pintype "bidirectional"))
    )
    (net (code "97") (name "/SDRAM_CS") (class "Default")
      (node (ref "IC8") (pin "E1") (pinfunction "GPIO_EMC_29_E1") (pintype "bidirectional"))
    )
    (net (code "98") (name "/SDRAM_DQ0") (class "Default")
      (node (ref "IC8") (pin "E3") (pinfunction "GPIO_EMC_00_E3") (pintype "bidirectional"))
    )
    (net (code "99") (name "/SDRAM_DQ1") (class "Default")
      (node (ref "IC8") (pin "F3") (pinfunction "GPIO_EMC_01_F3") (pintype "bidirectional"))
    )
    (net (code "100") (name "/SDRAM_DQ2") (class "Default")
      (node (ref "IC8") (pin "F4") (pinfunction "GPIO_EMC_02_F4") (pintype "bidirectional"))
    )
    (net (code "101") (name "/SDRAM_DQ3") (class "Default")
      (node (ref "IC8") (pin "G4") (pinfunction "GPIO_EMC_03_G4") (pintype "bidirectional"))
    )
    (net (code "102") (name "/SDRAM_DQ4") (class "Default")
      (node (ref "IC8") (pin "F2") (pinfunction "GPIO_EMC_04_F2") (pintype "bidirectional"))
    )
    (net (code "103") (name "/SDRAM_DQ5") (class "Default")
      (node (ref "IC8") (pin "G5") (pinfunction "GPIO_EMC_05_G5") (pintype "bidirectional"))
    )
    (net (code "104") (name "/SDRAM_DQ6") (class "Default")
      (node (ref "IC8") (pin "H5") (pinfunction "GPIO_EMC_06_H5") (pintype "bidirectional"))
    )
    (net (code "105") (name "/SDRAM_DQ7") (class "Default")
      (node (ref "IC8") (pin "H4") (pinfunction "GPIO_EMC_07_H4") (pintype "bidirectional"))
    )
    (net (code "106") (name "/SDRAM_DQ8") (class "Default")
      (node (ref "IC8") (pin "C6") (pinfunction "GPIO_EMC_30_C6") (pintype "bidirectional"))
    )
    (net (code "107") (name "/SDRAM_DQ9") (class "Default")
      (node (ref "IC8") (pin "C5") (pinfunction "GPIO_EMC_31_C5") (pintype "bidirectional"))
    )
    (net (code "108") (name "/SDRAM_DQ10") (class "Default")
      (node (ref "IC8") (pin "D5") (pinfunction "GPIO_EMC_32_D5") (pintype "bidirectional"))
    )
    (net (code "109") (name "/SDRAM_DQ11") (class "Default")
      (node (ref "IC8") (pin "C4") (pinfunction "GPIO_EMC_33_C4") (pintype "bidirectional"))
    )
    (net (code "110") (name "/SDRAM_DQ12") (class "Default")
      (node (ref "IC8") (pin "D4") (pinfunction "GPIO_EMC_34_D4") (pintype "bidirectional"))
    )
    (net (code "111") (name "/SDRAM_DQ13") (class "Default")
      (node (ref "IC8") (pin "E5") (pinfunction "GPIO_EMC_35_E5") (pintype "bidirectional"))
    )
    (net (code "112") (name "/SDRAM_DQ14") (class "Default")
      (node (ref "IC8") (pin "C3") (pinfunction "GPIO_EMC_36_C3") (pintype "bidirectional"))
    )
    (net (code "113") (name "/SDRAM_DQ15") (class "Default")
      (node (ref "IC8") (pin "E4") (pinfunction "GPIO_EMC_37_E4") (pintype "bidirectional"))
    )
    (net (code "114") (name "/SDRAM_DQMH") (class "Default")
      (node (ref "IC8") (pin "D6") (pinfunction "GPIO_EMC_38_D6") (pintype "bidirectional"))
    )
    (net (code "115") (name "/SDRAM_DQML") (class "Default")
      (node (ref "IC8") (pin "H3") (pinfunction "GPIO_EMC_08_H3") (pintype "bidirectional"))
    )
    (net (code "116") (name "/SDRAM_RAS") (class "Default")
      (node (ref "IC8") (pin "D2") (pinfunction "GPIO_EMC_25_D2") (pintype "bidirectional"))
    )
    (net (code "117") (name "/SDRAM_WE") (class "Default")
      (node (ref "IC8") (pin "D1") (pinfunction "GPIO_EMC_28_D1") (pintype "bidirectional"))
    )
    (net (code "118") (name "/SD_CD") (class "Default")
      (node (ref "IC8") (pin "L11") (pinfunction "GPIO_AD_B1_02_L11") (pintype "bidirectional"))
    )
    (net (code "119") (name "/SD_CLK") (class "Default")
      (node (ref "IC8") (pin "J3") (pinfunction "GPIO_SD_B0_01_J3") (pintype "bidirectional"))
    )
    (net (code "120") (name "/SD_CMD") (class "Default")
      (node (ref "IC8") (pin "J4") (pinfunction "GPIO_SD_B0_00_J4") (pintype "bidirectional"))
    )
    (net (code "121") (name "/SD_DAT0") (class "Default")
      (node (ref "IC8") (pin "J1") (pinfunction "GPIO_SD_B0_02_J1") (pintype "bidirectional"))
    )
    (net (code "122") (name "/SD_DAT1") (class "Default")
      (node (ref "IC8") (pin "K1") (pinfunction "GPIO_SD_B0_03_K1") (pintype "bidirectional"))
    )
    (net (code "123") (name "/SD_DAT2") (class "Default")
      (node (ref "IC8") (pin "H2") (pinfunction "GPIO_SD_B0_04_H2") (pintype "bidirectional"))
    )
    (net (code "124") (name "/SD_DAT3") (class "Default")
      (node (ref "IC8") (pin "J2") (pinfunction "GPIO_SD_B0_05_J2") (pintype "bidirectional"))
    )
    (net (code "125") (name "/SWITCH") (class "Default")
      (node (ref "R67") (pin "1") (pinfunction "1_1") (pintype "passive"))
      (node (ref "R68") (pin "1") (pinfunction "1_1") (pintype "passive"))
      (node (ref "S1") (pin "2") (pinfunction "COM_2") (pintype "passive"))
      (node (ref "S1") (pin "3") (pinfunction "COM_3") (pintype "passive"))
      (node (ref "S1") (pin "4") (pinfunction "COM_4") (pintype "passive"))
    )
    (net (code "126") (name "/SWITCH_OUT") (class "Default")
      (node (ref "C25") (pin "2") (pinfunction "2_2") (pintype "passive"))
      (node (ref "R68") (pin "2") (pinfunction "2_2") (pintype "passive"))
      (node (ref "R69") (pin "1") (pinfunction "1_1") (pintype "passive"))
    )
    (net (code "127") (name "/USB_D_N") (class "Default")
      (node (ref "IC8") (pin "M8") (pinfunction "USB_OTG1_DN_M8") (pintype "bidirectional"))
    )
    (net (code "128") (name "/USB_D_P") (class "Default")
      (node (ref "IC8") (pin "L8") (pinfunction "USB_OTG1_DP_L8") (pintype "bidirectional"))
    )
    (net (code "129") (name "/VBUS") (class "Default")
      (node (ref "C88") (pin "1") (pinfunction "1_1") (pintype "passive"))
      (node (ref "C95") (pin "2") (pinfunction "2_2") (pintype "passive"))
      (node (ref "IC8") (pin "N6") (pinfunction "USB_OTG1_VBUS_N6") (pintype "bidirectional"))
    )
    (net (code "130") (name "/VCC_SOC") (class "Default")
      (node (ref "C100") (pin "2") (pinfunction "2_2") (pintype "passive"))
      (node (ref "C103") (pin "2") (pinfunction "2_2") (pintype "passive"))
      (node (ref "C34") (pin "1") (pinfunction "1_1") (pintype "passive"))
      (node (ref "C38") (pin "1") (pinfunction "1_1") (pintype "passive"))
      (node (ref "C45") (pin "1") (pinfunction "1_1") (pintype "passive"))
      (node (ref "C46") (pin "2") (pinfunction "2_2") (pintype "passive"))
      (node (ref "C47") (pin "1") (pinfunction "1_1") (pintype "passive"))
      (node (ref "C48") (pin "1") (pinfunction "1_1") (pintype "passive"))
      (node (ref "C49") (pin "2") (pinfunction "2_2") (pintype "passive"))
      (node (ref "C87") (pin "2") (pinfunction "2_2") (pintype "passive"))
      (node (ref "C94") (pin "2") (pinfunction "2_2") (pintype "passive"))
      (node (ref "C97") (pin "2") (pinfunction "2_2") (pintype "passive"))
      (node (ref "C98") (pin "2") (pinfunction "2_2") (pintype "passive"))
      (node (ref "IC8") (pin "F6") (pinfunction "VDD_SOC_IN_1_F6") (pintype "bidirectional"))
      (node (ref "IC8") (pin "F7") (pinfunction "VDD_SOC_IN_2_F7") (pintype "bidirectional"))
      (node (ref "IC8") (pin "F8") (pinfunction "VDD_SOC_IN_3_F8") (pintype "bidirectional"))
      (node (ref "IC8") (pin "F9") (pinfunction "VDD_SOC_IN_4_F9") (pintype "bidirectional"))
      (node (ref "IC8") (pin "G6") (pinfunction "VDD_SOC_IN_5_G6") (pintype "bidirectional"))
      (node (ref "IC8") (pin "G9") (pinfunction "VDD_SOC_IN_6_G9") (pintype "bidirectional"))
      (node (ref "IC8") (pin "H6") (pinfunction "VDD_SOC_IN_7_H6") (pintype "bidirectional"))
      (node (ref "IC8") (pin "H9") (pinfunction "VDD_SOC_IN_8_H9") (pintype "bidirectional"))
      (node (ref "IC8") (pin "J5") (pinfunction "DCDC_SENSE_J5") (pintype "bidirectional"))
      (node (ref "IC8") (pin "J9") (pinfunction "VDD_SOC_IN_9_J9") (pintype "bidirectional"))
      (node (ref "L5") (pin "1") (pinfunction "1_1") (pintype "passive"))
    )
    (net (code "131") (name "/VDDA_ADC_3P3") (class "Default")
      (node (ref "C59") (pin "1") (pinfunction "1_1") (pintype "passive"))
      (node (ref "C60") (pin "2") (pinfunction "2_2") (pintype "passive"))
      (node (ref "C61") (pin "2") (pinfunction "2_2") (pintype "passive"))
      (node (ref "IC8") (pin "N14") (pinfunction "VDDA_ADC_3P3_N14") (pintype "bidirectional"))
      (node (ref "L6") (pin "1") (pinfunction "1_1") (pintype "passive"))
    )
    (net (code "132") (name "/VDD_HIGH_CAP") (class "Default")
      (node (ref "C101") (pin "2") (pinfunction "2_2") (pintype "passive"))
      (node (ref "C102") (pin "1") (pinfunction "1_1") (pintype "passive"))
      (node (ref "IC8") (pin "P8") (pinfunction "VDD_HIGH_CAP_P8") (pintype "bidirectional"))
    )
    (net (code "133") (name "/VDD_SNVS_CAP") (class "Default")
      (node (ref "C70") (pin "1") (pinfunction "1_1") (pintype "passive"))
      (node (ref "IC8") (pin "M10") (pinfunction "VDD_SNVS_CAP_M10") (pintype "bidirectional"))
    )
    (net (code "134") (name "/VDD_USB_CAP") (class "Default")
      (node (ref "C71") (pin "1") (pinfunction "1_1") (pintype "passive"))
      (node (ref "C72") (pin "2") (pinfunction "2_2") (pintype "passive"))
      (node (ref "C73") (pin "2") (pinfunction "2_2") (pintype "passive"))
      (node (ref "IC8") (pin "K8") (pinfunction "VDD_USB_CAP_K8") (pintype "bidirectional"))
    )
    (net (code "135") (name "/WAKEUP") (class "Default")
      (node (ref "IC8") (pin "L6") (pinfunction "WAKEUP_L6") (pintype "bidirectional"))
    )
    (net (code "136") (name "/WIFI_CLK") (class "Default")
      (node (ref "IC8") (pin "M13") (pinfunction "GPIO_AD_B1_09_M13") (pintype "bidirectional"))
    )
    (net (code "137") (name "/WIFI_CMD") (class "Default")
      (node (ref "IC8") (pin "H13") (pinfunction "GPIO_AD_B1_08_H13") (pintype "bidirectional"))
    )
    (net (code "138") (name "/WIFI_D0") (class "Default")
      (node (ref "IC8") (pin "M4") (pinfunction "GPIO_SD_B1_03_M4") (pintype "bidirectional"))
    )
    (net (code "139") (name "/WIFI_D1") (class "Default")
      (node (ref "IC8") (pin "M3") (pinfunction "GPIO_SD_B1_02_M3") (pintype "bidirectional"))
    )
    (net (code "140") (name "/WIFI_D2") (class "Default")
      (node (ref "IC8") (pin "J12") (pinfunction "GPIO_AD_B1_06_J12") (pintype "bidirectional"))
    )
    (net (code "141") (name "/WIFI_D3") (class "Default")
      (node (ref "IC8") (pin "K10") (pinfunction "GPIO_AD_B1_07_K10") (pintype "bidirectional"))
    )
    (net (code "142") (name "/WL_H_WAKE") (class "Default")
      (node (ref "IC8") (pin "E11") (pinfunction "GPIO_B0_15_E11") (pintype "bidirectional"))
    )
    (net (code "143") (name "/WL_REG_ON") (class "Default")
      (node (ref "IC8") (pin "E10") (pinfunction "GPIO_B0_14_E10") (pintype "bidirectional"))
    )
    (net (code "144") (name "/XTALI") (class "Default")
      (node (ref "C106") (pin "1") (pinfunction "1_1") (pintype "passive"))
      (node (ref "IC8") (pin "P11") (pinfunction "XTALI_P11") (pintype "bidirectional"))
      (node (ref "R40") (pin "1") (pinfunction "1_1") (pintype "passive"))
      (node (ref "Y2") (pin "3") (pinfunction "CRYSTAL_2_3") (pintype "bidirectional"))
    )
    (net (code "145") (name "/XTALO") (class "Default")
      (node (ref "C105") (pin "1") (pinfunction "1_1") (pintype "passive"))
      (node (ref "IC8") (pin "N11") (pinfunction "XTALO_N11") (pintype "bidirectional"))
      (node (ref "Y2") (pin "1") (pinfunction "CRYSTAL_1_1") (pintype "bidirectional"))
    )
    (net (code "146") (name "GND") (class "Default")
      (node (ref "C100") (pin "1") (pinfunction "1_1") (pintype "passive"))
      (node (ref "C101") (pin "1") (pinfunction "1_1") (pintype "passive"))
      (node (ref "C102") (pin "2") (pinfunction "2_2") (pintype "passive"))
      (node (ref "C103") (pin "1") (pinfunction "1_1") (pintype "passive"))
      (node (ref "C104") (pin "1") (pinfunction "1_1") (pintype "passive"))
      (node (ref "C105") (pin "2") (pinfunction "2_2") (pintype "passive"))
      (node (ref "C106") (pin "2") (pinfunction "2_2") (pintype "passive"))
      (node (ref "C107") (pin "2") (pinfunction "2_2") (pintype "passive"))
      (node (ref "C108") (pin "1") (pinfunction "1_1") (pintype "passive"))
      (node (ref "C109") (pin "2") (pinfunction "2_2") (pintype "passive"))
      (node (ref "C25") (pin "1") (pinfunction "1_1") (pintype "passive"))
      (node (ref "C34") (pin "2") (pinfunction "2_2") (pintype "passive"))
      (node (ref "C38") (pin "2") (pinfunction "2_2") (pintype "passive"))
      (node (ref "C41") (pin "1") (pinfunction "1_1") (pintype "passive"))
      (node (ref "C43") (pin "2") (pinfunction "2_2") (pintype "passive"))
      (node (ref "C45") (pin "2") (pinfunction "2_2") (pintype "passive"))
      (node (ref "C46") (pin "1") (pinfunction "1_1") (pintype "passive"))
      (node (ref "C47") (pin "2") (pinfunction "2_2") (pintype "passive"))
      (node (ref "C48") (pin "2") (pinfunction "2_2") (pintype "passive"))
      (node (ref "C49") (pin "1") (pinfunction "1_1") (pintype "passive"))
      (node (ref "C50") (pin "2") (pinfunction "2_2") (pintype "passive"))
      (node (ref "C53") (pin "2") (pinfunction "2_2") (pintype "passive"))
      (node (ref "C54") (pin "2") (pinfunction "2_2") (pintype "passive"))
      (node (ref "C55") (pin "2") (pinfunction "2_2") (pintype "passive"))
      (node (ref "C56") (pin "2") (pinfunction "2_2") (pintype "passive"))
      (node (ref "C57") (pin "1") (pinfunction "1_1") (pintype "passive"))
      (node (ref "C58") (pin "1") (pinfunction "1_1") (pintype "passive"))
      (node (ref "C59") (pin "2") (pinfunction "2_2") (pintype "passive"))
      (node (ref "C60") (pin "1") (pinfunction "1_1") (pintype "passive"))
      (node (ref "C61") (pin "1") (pinfunction "1_1") (pintype "passive"))
      (node (ref "C62") (pin "2") (pinfunction "2_2") (pintype "passive"))
      (node (ref "C63") (pin "2") (pinfunction "2_2") (pintype "passive"))
      (node (ref "C64") (pin "2") (pinfunction "2_2") (pintype "passive"))
      (node (ref "C66") (pin "1") (pinfunction "1_1") (pintype "passive"))
      (node (ref "C67") (pin "2") (pinfunction "2_2") (pintype "passive"))
      (node (ref "C68") (pin "1") (pinfunction "1_1") (pintype "passive"))
      (node (ref "C69") (pin "2") (pinfunction "2_2") (pintype "passive"))
      (node (ref "C70") (pin "2") (pinfunction "2_2") (pintype "passive"))
      (node (ref "C71") (pin "2") (pinfunction "2_2") (pintype "passive"))
      (node (ref "C72") (pin "1") (pinfunction "1_1") (pintype "passive"))
      (node (ref "C73") (pin "1") (pinfunction "1_1") (pintype "passive"))
      (node (ref "C79") (pin "2") (pinfunction "2_2") (pintype "passive"))
      (node (ref "C80") (pin "2") (pinfunction "2_2") (pintype "passive"))
      (node (ref "C86") (pin "1") (pinfunction "1_1") (pintype "passive"))
      (node (ref "C87") (pin "1") (pinfunction "1_1") (pintype "passive"))
      (node (ref "C88") (pin "2") (pinfunction "2_2") (pintype "passive"))
      (node (ref "C94") (pin "1") (pinfunction "1_1") (pintype "passive"))
      (node (ref "C95") (pin "1") (pinfunction "1_1") (pintype "passive"))
      (node (ref "C97") (pin "1") (pinfunction "1_1") (pintype "passive"))
      (node (ref "C98") (pin "1") (pinfunction "1_1") (pintype "passive"))
      (node (ref "C99") (pin "1") (pinfunction "1_1") (pintype "passive"))
      (node (ref "IC8") (pin "A1") (pinfunction "VSS_1_A1") (pintype "bidirectional"))
      (node (ref "IC8") (pin "A14") (pinfunction "VSS_2_A14") (pintype "bidirectional"))
      (node (ref "IC8") (pin "B10") (pinfunction "VSS_4_B10") (pintype "bidirectional"))
      (node (ref "IC8") (pin "B5") (pinfunction "VSS_3_B5") (pintype "bidirectional"))
      (node (ref "IC8") (pin "E13") (pinfunction "VSS_6_E13") (pintype "bidirectional"))
      (node (ref "IC8") (pin "E2") (pinfunction "VSS_5_E2") (pintype "bidirectional"))
      (node (ref "IC8") (pin "G7") (pinfunction "VSS_7_G7") (pintype "bidirectional"))
      (node (ref "IC8") (pin "G8") (pinfunction "VSS_8_G8") (pintype "bidirectional"))
      (node (ref "IC8") (pin "H7") (pinfunction "VSS_9_H7") (pintype "bidirectional"))
      (node (ref "IC8") (pin "H8") (pinfunction "VSS_10_H8") (pintype "bidirectional"))
      (node (ref "IC8") (pin "J7") (pinfunction "VSS_11_J7") (pintype "bidirectional"))
      (node (ref "IC8") (pin "J8") (pinfunction "VSS_12_J8") (pintype "bidirectional"))
      (node (ref "IC8") (pin "K13") (pinfunction "VSS_14_K13") (pintype "bidirectional"))
      (node (ref "IC8") (pin "K2") (pinfunction "VSS_13_K2") (pintype "bidirectional"))
      (node (ref "IC8") (pin "K6") (pinfunction "TEST_MODE_K6") (pintype "bidirectional"))
      (node (ref "IC8") (pin "K9") (pinfunction "NGND_KEL0_K9") (pintype "bidirectional"))
      (node (ref "IC8") (pin "L9") (pinfunction "VSS_15_L9") (pintype "bidirectional"))
      (node (ref "IC8") (pin "N1") (pinfunction "DCDC_GND_1_N1") (pintype "bidirectional"))
      (node (ref "IC8") (pin "N2") (pinfunction "DCDC_GND_2_N2") (pintype "bidirectional"))
      (node (ref "IC8") (pin "N5") (pinfunction "VSS_16_N5") (pintype "bidirectional"))
      (node (ref "IC8") (pin "N8") (pinfunction "VSS_17_N8") (pintype "bidirectional"))
      (node (ref "IC8") (pin "P1") (pinfunction "VSS_18_P1") (pintype "bidirectional"))
      (node (ref "IC8") (pin "P14") (pinfunction "VSS_19_P14") (pintype "bidirectional"))
      (node (ref "R40") (pin "2") (pinfunction "2_2") (pintype "passive"))
      (node (ref "S1") (pin "1") (pinfunction "NO_1") (pintype "passive"))
      (node (ref "S1") (pin "5") (pinfunction "NO_5") (pintype "passive"))
      (node (ref "S2") (pin "1") (pinfunction "NO_1") (pintype "passive"))
      (node (ref "S2") (pin "5") (pinfunction "NO_5") (pintype "passive"))
      (node (ref "Y2") (pin "2") (pinfunction "NC_1_2") (pintype "bidirectional"))
      (node (ref "Y2") (pin "4") (pinfunction "NC_2_4") (pintype "bidirectional"))
    )
    (net (code "147") (name "VCC") (class "Default")
      (node (ref "C108") (pin "2") (pinfunction "2_2") (pintype "passive"))
      (node (ref "C109") (pin "1") (pinfunction "1_1") (pintype "passive"))
      (node (ref "C41") (pin "2") (pinfunction "2_2") (pintype "passive"))
      (node (ref "C43") (pin "1") (pinfunction "1_1") (pintype "passive"))
      (node (ref "C50") (pin "1") (pinfunction "1_1") (pintype "passive"))
      (node (ref "C53") (pin "1") (pinfunction "1_1") (pintype "passive"))
      (node (ref "C54") (pin "1") (pinfunction "1_1") (pintype "passive"))
      (node (ref "C55") (pin "1") (pinfunction "1_1") (pintype "passive"))
      (node (ref "C56") (pin "1") (pinfunction "1_1") (pintype "passive"))
      (node (ref "C57") (pin "2") (pinfunction "2_2") (pintype "passive"))
      (node (ref "C58") (pin "2") (pinfunction "2_2") (pintype "passive"))
      (node (ref "C64") (pin "1") (pinfunction "1_1") (pintype "passive"))
      (node (ref "C66") (pin "2") (pinfunction "2_2") (pintype "passive"))
      (node (ref "C67") (pin "1") (pinfunction "1_1") (pintype "passive"))
      (node (ref "C68") (pin "2") (pinfunction "2_2") (pintype "passive"))
      (node (ref "C86") (pin "2") (pinfunction "2_2") (pintype "passive"))
      (node (ref "C99") (pin "2") (pinfunction "2_2") (pintype "passive"))
      (node (ref "IC8") (pin "E6") (pinfunction "NVCC_EMC_1_E6") (pintype "bidirectional"))
      (node (ref "IC8") (pin "E9") (pinfunction "NVCC_GPIO_1_E9") (pintype "bidirectional"))
      (node (ref "IC8") (pin "F10") (pinfunction "NVCC_GPIO_2_F10") (pintype "bidirectional"))
      (node (ref "IC8") (pin "F5") (pinfunction "NVCC_EMC_2_F5") (pintype "bidirectional"))
      (node (ref "IC8") (pin "J10") (pinfunction "NVCC_GPIO_3_J10") (pintype "bidirectional"))
      (node (ref "IC8") (pin "J6") (pinfunction "NVCC_SD0_J6") (pintype "bidirectional"))
      (node (ref "IC8") (pin "K4") (pinfunction "DCDC_IN_Q_K4") (pintype "bidirectional"))
      (node (ref "IC8") (pin "K5") (pinfunction "NVCC_SD1_K5") (pintype "bidirectional"))
      (node (ref "IC8") (pin "L1") (pinfunction "DCDC_IN_1_L1") (pintype "bidirectional"))
      (node (ref "IC8") (pin "L2") (pinfunction "DCDC_IN_2_L2") (pintype "bidirectional"))
      (node (ref "IC8") (pin "P12") (pinfunction "VDD_HIGH_IN_P12") (pintype "bidirectional"))
      (node (ref "L6") (pin "2") (pinfunction "2_2") (pintype "passive"))
      (node (ref "R32") (pin "2") (pinfunction "2_2") (pintype "passive"))
      (node (ref "R33") (pin "1") (pinfunction "1_1") (pintype "passive"))
      (node (ref "R67") (pin "2") (pinfunction "2_2") (pintype "passive"))
    )
    (net (code "148") (name "VDD_SNVS_CPU") (class "Default")
      (node (ref "C69") (pin "1") (pinfunction "1_1") (pintype "passive"))
      (node (ref "IC8") (pin "M9") (pinfunction "VDD_SNVS_IN_M9") (pintype "bidirectional"))
    )
    (net (code "149") (name "unconnected-(IC8-CCM_CLK1_N-PadP13)") (class "Default")
      (node (ref "IC8") (pin "P13") (pinfunction "CCM_CLK1_N_P13") (pintype "bidirectional"))
    )
    (net (code "150") (name "unconnected-(IC8-CCM_CLK1_P-PadN13)") (class "Default")
      (node (ref "IC8") (pin "N13") (pinfunction "CCM_CLK1_P_N13") (pintype "bidirectional"))
    )
    (net (code "151") (name "unconnected-(IC8-GPANAIO-PadN10)") (class "Default")
      (node (ref "IC8") (pin "N10") (pinfunction "GPANAIO_N10") (pintype "bidirectional"))
    )
    (net (code "152") (name "unconnected-(IC8-GPIO_EMC_39-PadB7)") (class "Default")
      (node (ref "IC8") (pin "B7") (pinfunction "GPIO_EMC_39_B7") (pintype "bidirectional"))
    )
    (net (code "153") (name "unconnected-(IC8-GPIO_SD_B1_05-PadN3)") (class "Default")
      (node (ref "IC8") (pin "N3") (pinfunction "GPIO_SD_B1_05_N3") (pintype "bidirectional"))
    )
    (net (code "154") (name "unconnected-(IC8-USB_OTG1_CHD_B-PadN12)") (class "Default")
      (node (ref "IC8") (pin "N12") (pinfunction "USB_OTG1_CHD_B_N12") (pintype "bidirectional"))
    )
    (net (code "155") (name "unconnected-(IC8-USB_OTG2_DN-PadN7)") (class "Default")
      (node (ref "IC8") (pin "N7") (pinfunction "USB_OTG2_DN_N7") (pintype "bidirectional"))
    )
    (net (code "156") (name "unconnected-(IC8-USB_OTG2_DP-PadP7)") (class "Default")
      (node (ref "IC8") (pin "P7") (pinfunction "USB_OTG2_DP_P7") (pintype "bidirectional"))
    )
    (net (code "157") (name "unconnected-(IC8-USB_OTG2_VBUS-PadP6)") (class "Default")
      (node (ref "IC8") (pin "P6") (pinfunction "USB_OTG2_VBUS_P6") (pintype "bidirectional"))
    )
  )
)
